# MSP430_BNC_breakout_v2.net
KiCad netlist of a schematic drawn in EAGLE
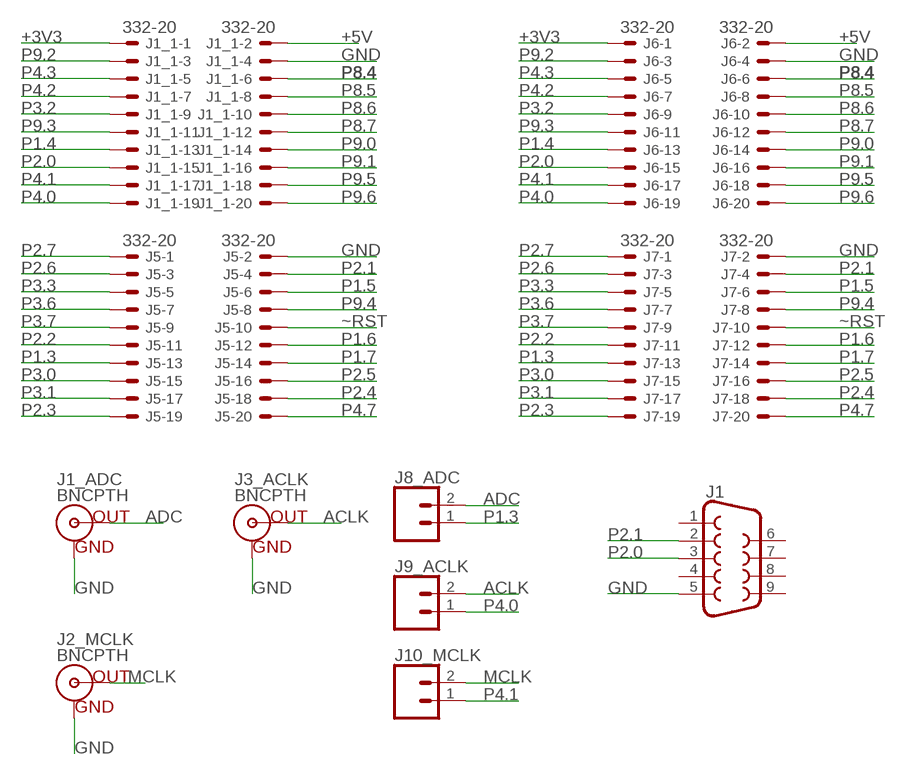
[diagram p0: schematic, sheet 1]

(export (version "E")
  (design (tool "Eeschema 10.0.6"))
  (components
    (comp (ref "J1")
      (value "DB9FEMALE")
      (footprint "eagle-import:DB9")
      (libsource (lib "eagle-import") (part "DB9FEMALE"))
    )
    (comp (ref "J1_1")
      (value "332-20")
      (footprint "eagle-import:332-20")
      (libsource (lib "eagle-import") (part "332-20"))
    )
    (comp (ref "J1_ADC")
      (value "BNCPTH")
      (footprint "eagle-import:BNC")
      (libsource (lib "eagle-import") (part "BNCPTH"))
    )
    (comp (ref "J2_MCLK")
      (value "BNCPTH")
      (footprint "eagle-import:BNC")
      (libsource (lib "eagle-import") (part "BNCPTH"))
    )
    (comp (ref "J3_ACLK")
      (value "BNCPTH")
      (footprint "eagle-import:BNC")
      (libsource (lib "eagle-import") (part "BNCPTH"))
    )
    (comp (ref "J5")
      (value "332-20")
      (footprint "eagle-import:332-20")
      (libsource (lib "eagle-import") (part "332-20"))
    )
    (comp (ref "J6")
      (value "332-20")
      (footprint "eagle-import:332-20")
      (libsource (lib "eagle-import") (part "332-20"))
    )
    (comp (ref "J7")
      (value "332-20")
      (footprint "eagle-import:332-20")
      (libsource (lib "eagle-import") (part "332-20"))
    )
    (comp (ref "J8_ADC")
      (value "CONN_02")
      (footprint "eagle-import:1X02")
      (libsource (lib "eagle-import") (part "CONN_02"))
    )
    (comp (ref "J9_ACLK")
      (value "CONN_02")
      (footprint "eagle-import:1X02")
      (libsource (lib "eagle-import") (part "CONN_02"))
    )
    (comp (ref "J10_MCLK")
      (value "CONN_02")
      (footprint "eagle-import:1X02")
      (libsource (lib "eagle-import") (part "CONN_02"))
    )
  )
  (nets
    (net (code "1") (name "/+3V3") (class "Default")
      (node (ref "J1_1") (pin "1") (pinfunction "S_1") (pintype "passive"))
      (node (ref "J6") (pin "1") (pinfunction "S_1") (pintype "passive"))
    )
    (net (code "2") (name "/+5V") (class "Default")
      (node (ref "J1_1") (pin "2") (pinfunction "S_2") (pintype "passive"))
      (node (ref "J6") (pin "2") (pinfunction "S_2") (pintype "passive"))
    )
    (net (code "3") (name "/ACLK") (class "Default")
      (node (ref "J3_ACLK") (pin "S") (pinfunction "OUT_S") (pintype "bidirectional"))
      (node (ref "J9_ACLK") (pin "2") (pinfunction "2_2") (pintype "passive"))
    )
    (net (code "4") (name "/ADC") (class "Default")
      (node (ref "J1_ADC") (pin "S") (pinfunction "OUT_S") (pintype "bidirectional"))
      (node (ref "J8_ADC") (pin "2") (pinfunction "2_2") (pintype "passive"))
    )
    (net (code "5") (name "/GND") (class "Default")
      (node (ref "J1") (pin "5") (pinfunction "5_5") (pintype "passive"))
      (node (ref "J1_1") (pin "4") (pinfunction "S_4") (pintype "passive"))
      (node (ref "J1_ADC") (pin "GND") (pinfunction "GND_GND") (pintype "bidirectional"))
      (node (ref "J2_MCLK") (pin "GND") (pinfunction "GND_GND") (pintype "bidirectional"))
      (node (ref "J3_ACLK") (pin "GND") (pinfunction "GND_GND") (pintype "bidirectional"))
      (node (ref "J5") (pin "2") (pinfunction "S_2") (pintype "passive"))
      (node (ref "J6") (pin "4") (pinfunction "S_4") (pintype "passive"))
      (node (ref "J7") (pin "2") (pinfunction "S_2") (pintype "passive"))
    )
    (net (code "6") (name "/MCLK") (class "Default")
      (node (ref "J10_MCLK") (pin "2") (pinfunction "2_2") (pintype "passive"))
      (node (ref "J2_MCLK") (pin "S") (pinfunction "OUT_S") (pintype "bidirectional"))
    )
    (net (code "7") (name "/P1.3") (class "Default")
      (node (ref "J5") (pin "13") (pinfunction "S_13") (pintype "passive"))
      (node (ref "J7") (pin "13") (pinfunction "S_13") (pintype "passive"))
      (node (ref "J8_ADC") (pin "1") (pinfunction "1_1") (pintype "passive"))
    )
    (net (code "8") (name "/P1.4") (class "Default")
      (node (ref "J1_1") (pin "13") (pinfunction "S_13") (pintype "passive"))
      (node (ref "J6") (pin "13") (pinfunction "S_13") (pintype "passive"))
    )
    (net (code "9") (name "/P1.5") (class "Default")
      (node (ref "J5") (pin "6") (pinfunction "S_6") (pintype "passive"))
      (node (ref "J7") (pin "6") (pinfunction "S_6") (pintype "passive"))
    )
    (net (code "10") (name "/P1.6") (class "Default")
      (node (ref "J5") (pin "12") (pinfunction "S_12") (pintype "passive"))
      (node (ref "J7") (pin "12") (pinfunction "S_12") (pintype "passive"))
    )
    (net (code "11") (name "/P1.7") (class "Default")
      (node (ref "J5") (pin "14") (pinfunction "S_14") (pintype "passive"))
      (node (ref "J7") (pin "14") (pinfunction "S_14") (pintype "passive"))
    )
    (net (code "12") (name "/P2.0") (class "Default")
      (node (ref "J1") (pin "3") (pinfunction "3_3") (pintype "passive"))
      (node (ref "J1_1") (pin "15") (pinfunction "S_15") (pintype "passive"))
      (node (ref "J6") (pin "15") (pinfunction "S_15") (pintype "passive"))
    )
    (net (code "13") (name "/P2.1") (class "Default")
      (node (ref "J1") (pin "2") (pinfunction "2_2") (pintype "passive"))
      (node (ref "J5") (pin "4") (pinfunction "S_4") (pintype "passive"))
      (node (ref "J7") (pin "4") (pinfunction "S_4") (pintype "passive"))
    )
    (net (code "14") (name "/P2.2") (class "Default")
      (node (ref "J5") (pin "11") (pinfunction "S_11") (pintype "passive"))
      (node (ref "J7") (pin "11") (pinfunction "S_11") (pintype "passive"))
    )
    (net (code "15") (name "/P2.3") (class "Default")
      (node (ref "J5") (pin "19") (pinfunction "S_19") (pintype "passive"))
      (node (ref "J7") (pin "19") (pinfunction "S_19") (pintype "passive"))
    )
    (net (code "16") (name "/P2.4") (class "Default")
      (node (ref "J5") (pin "18") (pinfunction "S_18") (pintype "passive"))
      (node (ref "J7") (pin "18") (pinfunction "S_18") (pintype "passive"))
    )
    (net (code "17") (name "/P2.5") (class "Default")
      (node (ref "J5") (pin "16") (pinfunction "S_16") (pintype "passive"))
      (node (ref "J7") (pin "16") (pinfunction "S_16") (pintype "passive"))
    )
    (net (code "18") (name "/P2.6") (class "Default")
      (node (ref "J5") (pin "3") (pinfunction "S_3") (pintype "passive"))
      (node (ref "J7") (pin "3") (pinfunction "S_3") (pintype "passive"))
    )
    (net (code "19") (name "/P2.7") (class "Default")
      (node (ref "J5") (pin "1") (pinfunction "S_1") (pintype "passive"))
      (node (ref "J7") (pin "1") (pinfunction "S_1") (pintype "passive"))
    )
    (net (code "20") (name "/P3.0") (class "Default")
      (node (ref "J5") (pin "15") (pinfunction "S_15") (pintype "passive"))
      (node (ref "J7") (pin "15") (pinfunction "S_15") (pintype "passive"))
    )
    (net (code "21") (name "/P3.1") (class "Default")
      (node (ref "J5") (pin "17") (pinfunction "S_17") (pintype "passive"))
      (node (ref "J7") (pin "17") (pinfunction "S_17") (pintype "passive"))
    )
    (net (code "22") (name "/P3.2") (class "Default")
      (node (ref "J1_1") (pin "9") (pinfunction "S_9") (pintype "passive"))
      (node (ref "J6") (pin "9") (pinfunction "S_9") (pintype "passive"))
    )
    (net (code "23") (name "/P3.3") (class "Default")
      (node (ref "J5") (pin "5") (pinfunction "S_5") (pintype "passive"))
      (node (ref "J7") (pin "5") (pinfunction "S_5") (pintype "passive"))
    )
    (net (code "24") (name "/P3.6") (class "Default")
      (node (ref "J5") (pin "7") (pinfunction "S_7") (pintype "passive"))
      (node (ref "J7") (pin "7") (pinfunction "S_7") (pintype "passive"))
    )
    (net (code "25") (name "/P3.7") (class "Default")
      (node (ref "J5") (pin "9") (pinfunction "S_9") (pintype "passive"))
      (node (ref "J7") (pin "9") (pinfunction "S_9") (pintype "passive"))
    )
    (net (code "26") (name "/P4.0") (class "Default")
      (node (ref "J1_1") (pin "19") (pinfunction "S_19") (pintype "passive"))
      (node (ref "J6") (pin "19") (pinfunction "S_19") (pintype "passive"))
      (node (ref "J9_ACLK") (pin "1") (pinfunction "1_1") (pintype "passive"))
    )
    (net (code "27") (name "/P4.1") (class "Default")
      (node (ref "J10_MCLK") (pin "1") (pinfunction "1_1") (pintype "passive"))
      (node (ref "J1_1") (pin "17") (pinfunction "S_17") (pintype "passive"))
      (node (ref "J6") (pin "17") (pinfunction "S_17") (pintype "passive"))
    )
    (net (code "28") (name "/P4.2") (class "Default")
      (node (ref "J1_1") (pin "7") (pinfunction "S_7") (pintype "passive"))
      (node (ref "J6") (pin "7") (pinfunction "S_7") (pintype "passive"))
    )
    (net (code "29") (name "/P4.3") (class "Default")
      (node (ref "J1_1") (pin "5") (pinfunction "S_5") (pintype "passive"))
      (node (ref "J6") (pin "5") (pinfunction "S_5") (pintype "passive"))
    )
    (net (code "30") (name "/P4.7") (class "Default")
      (node (ref "J5") (pin "20") (pinfunction "S_20") (pintype "passive"))
      (node (ref "J7") (pin "20") (pinfunction "S_20") (pintype "passive"))
    )
    (net (code "31") (name "/P8.4") (class "Default")
      (node (ref "J1_1") (pin "6") (pinfunction "S_6") (pintype "passive"))
      (node (ref "J6") (pin "6") (pinfunction "S_6") (pintype "passive"))
    )
    (net (code "32") (name "/P8.5") (class "Default")
      (node (ref "J1_1") (pin "8") (pinfunction "S_8") (pintype "passive"))
      (node (ref "J6") (pin "8") (pinfunction "S_8") (pintype "passive"))
    )
    (net (code "33") (name "/P8.6") (class "Default")
      (node (ref "J1_1") (pin "10") (pinfunction "S_10") (pintype "passive"))
      (node (ref "J6") (pin "10") (pinfunction "S_10") (pintype "passive"))
    )
    (net (code "34") (name "/P8.7") (class "Default")
      (node (ref "J1_1") (pin "12") (pinfunction "S_12") (pintype "passive"))
      (node (ref "J6") (pin "12") (pinfunction "S_12") (pintype "passive"))
    )
    (net (code "35") (name "/P9.0") (class "Default")
      (node (ref "J1_1") (pin "14") (pinfunction "S_14") (pintype "passive"))
      (node (ref "J6") (pin "14") (pinfunction "S_14") (pintype "passive"))
    )
    (net (code "36") (name "/P9.1") (class "Default")
      (node (ref "J1_1") (pin "16") (pinfunction "S_16") (pintype "passive"))
      (node (ref "J6") (pin "16") (pinfunction "S_16") (pintype "passive"))
    )
    (net (code "37") (name "/P9.2") (class "Default")
      (node (ref "J1_1") (pin "3") (pinfunction "S_3") (pintype "passive"))
      (node (ref "J6") (pin "3") (pinfunction "S_3") (pintype "passive"))
    )
    (net (code "38") (name "/P9.3") (class "Default")
      (node (ref "J1_1") (pin "11") (pinfunction "S_11") (pintype "passive"))
      (node (ref "J6") (pin "11") (pinfunction "S_11") (pintype "passive"))
    )
    (net (code "39") (name "/P9.4") (class "Default")
      (node (ref "J5") (pin "8") (pinfunction "S_8") (pintype "passive"))
      (node (ref "J7") (pin "8") (pinfunction "S_8") (pintype "passive"))
    )
    (net (code "40") (name "/P9.5") (class "Default")
      (node (ref "J1_1") (pin "18") (pinfunction "S_18") (pintype "passive"))
      (node (ref "J6") (pin "18") (pinfunction "S_18") (pintype "passive"))
    )
    (net (code "41") (name "/P9.6") (class "Default")
      (node (ref "J1_1") (pin "20") (pinfunction "S_20") (pintype "passive"))
      (node (ref "J6") (pin "20") (pinfunction "S_20") (pintype "passive"))
    )
    (net (code "42") (name "/~{RST}") (class "Default")
      (node (ref "J5") (pin "10") (pinfunction "S_10") (pintype "passive"))
      (node (ref "J7") (pin "10") (pinfunction "S_10") (pintype "passive"))
    )
    (net (code "43") (name "unconnected-(J1-Pad1)") (class "Default")
      (node (ref "J1") (pin "1") (pinfunction "1_1") (pintype "passive"))
    )
    (net (code "44") (name "unconnected-(J1-Pad4)") (class "Default")
      (node (ref "J1") (pin "4") (pinfunction "4_4") (pintype "passive"))
    )
    (net (code "45") (name "unconnected-(J1-Pad6)") (class "Default")
      (node (ref "J1") (pin "6") (pinfunction "6_6") (pintype "passive"))
    )
    (net (code "46") (name "unconnected-(J1-Pad7)") (class "Default")
      (node (ref "J1") (pin "7") (pinfunction "7_7") (pintype "passive"))
    )
    (net (code "47") (name "unconnected-(J1-Pad8)") (class "Default")
      (node (ref "J1") (pin "8") (pinfunction "8_8") (pintype "passive"))
    )
    (net (code "48") (name "unconnected-(J1-Pad9)") (class "Default")
      (node (ref "J1") (pin "9") (pinfunction "9_9") (pintype "passive"))
    )
  )
)
